# SX1308.net
KiCad netlist of a schematic drawn in Altium Designer
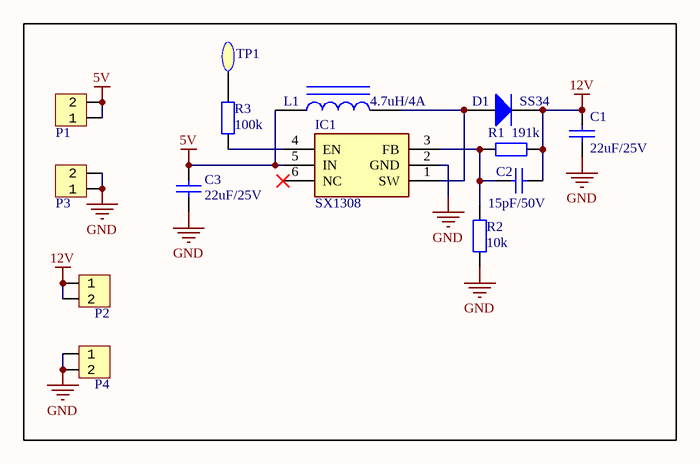
[diagram p0: SX1308.SchDoc]

(export (version "E")
  (design (tool "Eeschema 10.0.6"))
  (components
    (comp (ref "C1")
      (value "22uF/25V")
      (footprint "CAP-0603")
      (description "X7R")
      (libsource (lib "Power_Lib_Altium") (part "CAP"))
    )
    (comp (ref "C2")
      (value "15pF/50V")
      (footprint "CAP-0603")
      (description "NPO")
      (libsource (lib "Power_Lib_Altium") (part "CAP"))
    )
    (comp (ref "C3")
      (value "22uF/25V")
      (footprint "CAP-0603")
      (description "X7R")
      (libsource (lib "Power_Lib_Altium") (part "CAP"))
    )
    (comp (ref "D1")
      (value "SS34")
      (footprint "DO-214AC_SMA")
      (description "肖特基二极管")
      (libsource (lib "Power_Lib_Altium") (part "DIODE"))
    )
    (comp (ref "IC1")
      (value "SX1308")
      (footprint "SOT-23-6")
      (description "集成升压芯片")
      (libsource (lib "Power_Lib_Altium") (part "SX1308"))
    )
    (comp (ref "L1")
      (value "4.7uH/4A")
      (footprint "SMD_7.3x7.3x4.2mm")
      (description "电感")
      (libsource (lib "Power_Lib_Altium") (part "INDUCTOR"))
    )
    (comp (ref "P1")
      (value "HDR1x2_2.54")
      (footprint "HDR1X2_2.54_180")
      (description "Header")
      (libsource (lib "") (part "HDR1x2_2.54_1"))
    )
    (comp (ref "P2")
      (value "HDR1x2_2.54")
      (footprint "HDR1X2_2.54_180")
      (description "Header")
      (libsource (lib "Power_Lib_Altium") (part "HDR1x2_2.54"))
    )
    (comp (ref "P3")
      (value "HDR1x2_2.54")
      (footprint "HDR1X2_2.54_180")
      (description "Header")
      (libsource (lib "") (part "HDR1x2_2.54_1"))
    )
    (comp (ref "P4")
      (value "HDR1x2_2.54")
      (footprint "HDR1X2_2.54_180")
      (description "Header")
      (libsource (lib "Power_Lib_Altium") (part "HDR1x2_2.54"))
    )
    (comp (ref "R1")
      (value "191k")
      (footprint "R-0603")
      (description "贴片电阻")
      (libsource (lib "Power_Lib_Altium") (part "RES"))
    )
    (comp (ref "R2")
      (value "10k")
      (footprint "R-0603")
      (description "贴片电阻")
      (libsource (lib "") (part "RES_1"))
    )
    (comp (ref "R3")
      (value "100k")
      (footprint "R-0603")
      (description "贴片电阻")
      (libsource (lib "") (part "RES_2"))
    )
    (comp (ref "TP1")
      (value "TestPoint")
      (footprint "TestPoint")
      (description "测试点")
      (libsource (lib "Power_Lib_Altium") (part "TestPoint"))
    )
  )
  (nets
    (net (code "1") (name "5V") (class "Default")
      (node (ref "C3") (pin "2") (pinfunction "2_2") (pintype "passive"))
      (node (ref "IC1") (pin "5") (pinfunction "IN_5") (pintype "passive"))
      (node (ref "L1") (pin "1") (pinfunction "1_1") (pintype "passive"))
      (node (ref "P1") (pin "1") (pinfunction "1_1") (pintype "passive"))
      (node (ref "P1") (pin "2") (pinfunction "2_2") (pintype "passive"))
    )
    (net (code "2") (name "12V") (class "Default")
      (node (ref "C1") (pin "2") (pinfunction "2_2") (pintype "passive"))
      (node (ref "C2") (pin "2") (pinfunction "2_2") (pintype "passive"))
      (node (ref "D1") (pin "2") (pinfunction "K_2") (pintype "passive"))
      (node (ref "P2") (pin "1") (pinfunction "1_1") (pintype "passive"))
      (node (ref "P2") (pin "2") (pinfunction "2_2") (pintype "passive"))
      (node (ref "R1") (pin "2") (pinfunction "2_2") (pintype "passive"))
    )
    (net (code "3") (name "GND") (class "Default")
      (node (ref "C1") (pin "1") (pinfunction "1_1") (pintype "passive"))
      (node (ref "C3") (pin "1") (pinfunction "1_1") (pintype "passive"))
      (node (ref "IC1") (pin "2") (pinfunction "GND_2") (pintype "passive"))
      (node (ref "P3") (pin "1") (pinfunction "1_1") (pintype "passive"))
      (node (ref "P3") (pin "2") (pinfunction "2_2") (pintype "passive"))
      (node (ref "P4") (pin "1") (pinfunction "1_1") (pintype "passive"))
      (node (ref "P4") (pin "2") (pinfunction "2_2") (pintype "passive"))
      (node (ref "R2") (pin "1") (pinfunction "1_1") (pintype "passive"))
    )
    (net (code "4") (name "Net-(D1-A)") (class "Default")
      (node (ref "D1") (pin "1") (pinfunction "A_1") (pintype "passive"))
      (node (ref "IC1") (pin "1") (pinfunction "SW_1") (pintype "passive"))
      (node (ref "L1") (pin "2") (pinfunction "2_2") (pintype "passive"))
    )
    (net (code "5") (name "Net-(IC1-EN)") (class "Default")
      (node (ref "IC1") (pin "4") (pinfunction "EN_4") (pintype "passive"))
      (node (ref "R3") (pin "2") (pinfunction "2_2") (pintype "passive"))
    )
    (net (code "6") (name "Net-(IC1-FB)") (class "Default")
      (node (ref "C2") (pin "1") (pinfunction "1_1") (pintype "passive"))
      (node (ref "IC1") (pin "3") (pinfunction "FB_3") (pintype "passive"))
      (node (ref "R1") (pin "1") (pinfunction "1_1") (pintype "passive"))
      (node (ref "R2") (pin "2") (pinfunction "2_2") (pintype "passive"))
    )
    (net (code "7") (name "Net-(R3-Pad1)") (class "Default")
      (node (ref "R3") (pin "1") (pinfunction "1_1") (pintype "passive"))
      (node (ref "TP1") (pin "1") (pinfunction "1_1") (pintype "passive"))
    )
    (net (code "8") (name "unconnected-(IC1-NC-Pad6)") (class "Default")
      (node (ref "IC1") (pin "6") (pinfunction "NC_6") (pintype "passive+no_connect"))
    )
  )
)
